# CAADIOESQV1_01-ADAPTADOR-MICRO-DIP28.net
KiCad netlist of a schematic drawn in Altium Designer
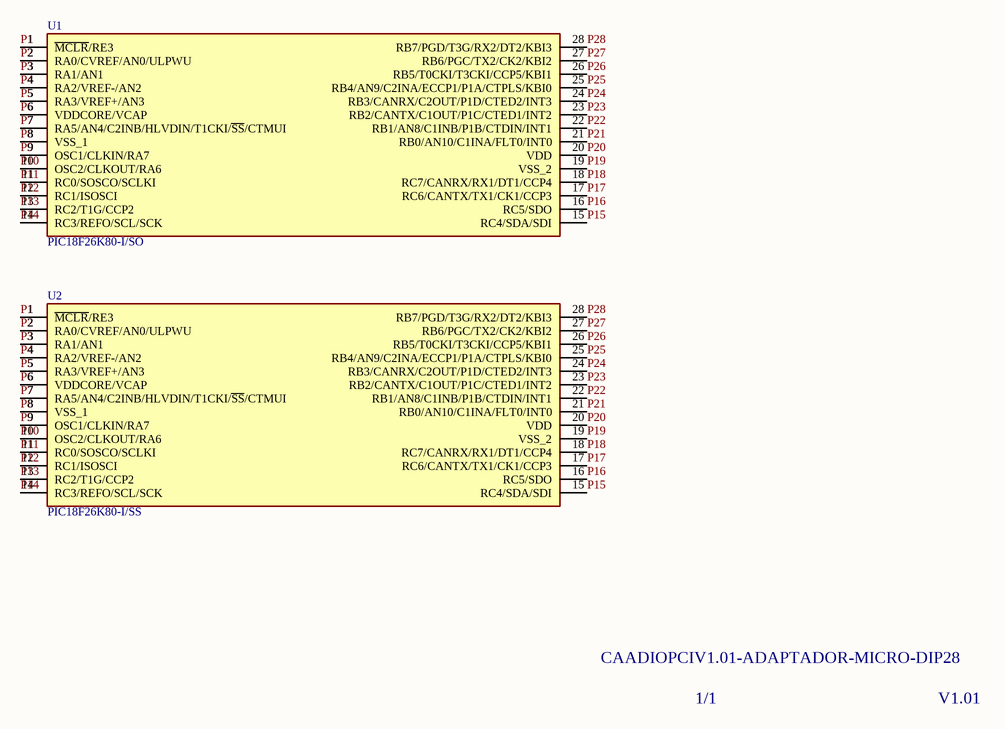
[diagram p0: CAADIOESQV1.01-ADAPTADOR-MICRO-DIP28.SchDoc]

(export (version "E")
  (design (tool "Eeschema 10.0.6"))
  (components
    (comp (ref "U1")
      (value "PIC18F26K80-I/SO")
      (footprint "SOIC-28")
      (description "Microcontrolador")
      (fields (field (name "MOUSER PART NUMBER") "579-PIC18F26K80-I/SO"))
      (libsource (lib "Lib SMD") (part "PIC18F26K80-I/SO"))
    )
    (comp (ref "U2")
      (value "PIC18F26K80-I/SS")
      (footprint "SSOP-28")
      (description "Microcontrolador")
      (fields (field (name "MOUSER PART NUMBER") "579-PIC18F26K80-I/SS"))
      (libsource (lib "Lib SMD") (part "PIC18F26K80-I/SS"))
    )
  )
  (nets
    (net (code "1") (name "/P1") (class "Default")
      (node (ref "U1") (pin "1") (pinfunction "~{MCLR}/RE3_1") (pintype "passive"))
      (node (ref "U2") (pin "1") (pinfunction "~{MCLR}/RE3_1") (pintype "passive"))
    )
    (net (code "2") (name "/P2") (class "Default")
      (node (ref "U1") (pin "2") (pinfunction "RA0/CVREF/AN0/ULPWU_2") (pintype "passive"))
      (node (ref "U2") (pin "2") (pinfunction "RA0/CVREF/AN0/ULPWU_2") (pintype "passive"))
    )
    (net (code "3") (name "/P3") (class "Default")
      (node (ref "U1") (pin "3") (pinfunction "RA1/AN1_3") (pintype "passive"))
      (node (ref "U2") (pin "3") (pinfunction "RA1/AN1_3") (pintype "passive"))
    )
    (net (code "4") (name "/P4") (class "Default")
      (node (ref "U1") (pin "4") (pinfunction "RA2/VREF-/AN2_4") (pintype "passive"))
      (node (ref "U2") (pin "4") (pinfunction "RA2/VREF-/AN2_4") (pintype "passive"))
    )
    (net (code "5") (name "/P5") (class "Default")
      (node (ref "U1") (pin "5") (pinfunction "RA3/VREF+/AN3_5") (pintype "passive"))
      (node (ref "U2") (pin "5") (pinfunction "RA3/VREF+/AN3_5") (pintype "passive"))
    )
    (net (code "6") (name "/P6") (class "Default")
      (node (ref "U1") (pin "6") (pinfunction "VDDCORE/VCAP_6") (pintype "passive"))
      (node (ref "U2") (pin "6") (pinfunction "VDDCORE/VCAP_6") (pintype "passive"))
    )
    (net (code "7") (name "/P7") (class "Default")
      (node (ref "U1") (pin "7") (pinfunction "RA5/AN4/C2INB/HLVDIN/T1CKI/~{SS}/CTMUI_7") (pintype "passive"))
      (node (ref "U2") (pin "7") (pinfunction "RA5/AN4/C2INB/HLVDIN/T1CKI/~{SS}/CTMUI_7") (pintype "passive"))
    )
    (net (code "8") (name "/P8") (class "Default")
      (node (ref "U1") (pin "8") (pinfunction "VSS_1_8") (pintype "passive"))
      (node (ref "U2") (pin "8") (pinfunction "VSS_1_8") (pintype "passive"))
    )
    (net (code "9") (name "/P9") (class "Default")
      (node (ref "U1") (pin "9") (pinfunction "OSC1/CLKIN/RA7_9") (pintype "passive"))
      (node (ref "U2") (pin "9") (pinfunction "OSC1/CLKIN/RA7_9") (pintype "passive"))
    )
    (net (code "10") (name "/P10") (class "Default")
      (node (ref "U1") (pin "10") (pinfunction "OSC2/CLKOUT/RA6_10") (pintype "passive"))
      (node (ref "U2") (pin "10") (pinfunction "OSC2/CLKOUT/RA6_10") (pintype "passive"))
    )
    (net (code "11") (name "/P11") (class "Default")
      (node (ref "U1") (pin "11") (pinfunction "RC0/SOSCO/SCLKI_11") (pintype "passive"))
      (node (ref "U2") (pin "11") (pinfunction "RC0/SOSCO/SCLKI_11") (pintype "passive"))
    )
    (net (code "12") (name "/P12") (class "Default")
      (node (ref "U1") (pin "12") (pinfunction "RC1/ISOSCI_12") (pintype "passive"))
      (node (ref "U2") (pin "12") (pinfunction "RC1/ISOSCI_12") (pintype "passive"))
    )
    (net (code "13") (name "/P13") (class "Default")
      (node (ref "U1") (pin "13") (pinfunction "RC2/T1G/CCP2_13") (pintype "passive"))
      (node (ref "U2") (pin "13") (pinfunction "RC2/T1G/CCP2_13") (pintype "passive"))
    )
    (net (code "14") (name "/P14") (class "Default")
      (node (ref "U1") (pin "14") (pinfunction "RC3/REFO/SCL/SCK_14") (pintype "passive"))
      (node (ref "U2") (pin "14") (pinfunction "RC3/REFO/SCL/SCK_14") (pintype "passive"))
    )
    (net (code "15") (name "/P15") (class "Default")
      (node (ref "U1") (pin "15") (pinfunction "RC4/SDA/SDI_15") (pintype "passive"))
      (node (ref "U2") (pin "15") (pinfunction "RC4/SDA/SDI_15") (pintype "passive"))
    )
    (net (code "16") (name "/P16") (class "Default")
      (node (ref "U1") (pin "16") (pinfunction "RC5/SDO_16") (pintype "passive"))
      (node (ref "U2") (pin "16") (pinfunction "RC5/SDO_16") (pintype "passive"))
    )
    (net (code "17") (name "/P17") (class "Default")
      (node (ref "U1") (pin "17") (pinfunction "RC6/CANTX/TX1/CK1/CCP3_17") (pintype "passive"))
      (node (ref "U2") (pin "17") (pinfunction "RC6/CANTX/TX1/CK1/CCP3_17") (pintype "passive"))
    )
    (net (code "18") (name "/P18") (class "Default")
      (node (ref "U1") (pin "18") (pinfunction "RC7/CANRX/RX1/DT1/CCP4_18") (pintype "passive"))
      (node (ref "U2") (pin "18") (pinfunction "RC7/CANRX/RX1/DT1/CCP4_18") (pintype "passive"))
    )
    (net (code "19") (name "/P19") (class "Default")
      (node (ref "U1") (pin "19") (pinfunction "VSS_2_19") (pintype "passive"))
      (node (ref "U2") (pin "19") (pinfunction "VSS_2_19") (pintype "passive"))
    )
    (net (code "20") (name "/P20") (class "Default")
      (node (ref "U1") (pin "20") (pinfunction "VDD_20") (pintype "passive"))
      (node (ref "U2") (pin "20") (pinfunction "VDD_20") (pintype "passive"))
    )
    (net (code "21") (name "/P21") (class "Default")
      (node (ref "U1") (pin "21") (pinfunction "RB0/AN10/C1INA/FLT0/INT0_21") (pintype "passive"))
      (node (ref "U2") (pin "21") (pinfunction "RB0/AN10/C1INA/FLT0/INT0_21") (pintype "passive"))
    )
    (net (code "22") (name "/P22") (class "Default")
      (node (ref "U1") (pin "22") (pinfunction "RB1/AN8/C1INB/P1B/CTDIN/INT1_22") (pintype "passive"))
      (node (ref "U2") (pin "22") (pinfunction "RB1/AN8/C1INB/P1B/CTDIN/INT1_22") (pintype "passive"))
    )
    (net (code "23") (name "/P23") (class "Default")
      (node (ref "U1") (pin "23") (pinfunction "RB2/CANTX/C1OUT/P1C/CTED1/INT2_23") (pintype "passive"))
      (node (ref "U2") (pin "23") (pinfunction "RB2/CANTX/C1OUT/P1C/CTED1/INT2_23") (pintype "passive"))
    )
    (net (code "24") (name "/P24") (class "Default")
      (node (ref "U1") (pin "24") (pinfunction "RB3/CANRX/C2OUT/P1D/CTED2/INT3_24") (pintype "passive"))
      (node (ref "U2") (pin "24") (pinfunction "RB3/CANRX/C2OUT/P1D/CTED2/INT3_24") (pintype "passive"))
    )
    (net (code "25") (name "/P25") (class "Default")
      (node (ref "U1") (pin "25") (pinfunction "RB4/AN9/C2INA/ECCP1/P1A/CTPLS/KBI0_25") (pintype "passive"))
      (node (ref "U2") (pin "25") (pinfunction "RB4/AN9/C2INA/ECCP1/P1A/CTPLS/KBI0_25") (pintype "passive"))
    )
    (net (code "26") (name "/P26") (class "Default")
      (node (ref "U1") (pin "26") (pinfunction "RB5/T0CKI/T3CKI/CCP5/KBI1_26") (pintype "passive"))
      (node (ref "U2") (pin "26") (pinfunction "RB5/T0CKI/T3CKI/CCP5/KBI1_26") (pintype "passive"))
    )
    (net (code "27") (name "/P27") (class "Default")
      (node (ref "U1") (pin "27") (pinfunction "RB6/PGC/TX2/CK2/KBI2_27") (pintype "passive"))
      (node (ref "U2") (pin "27") (pinfunction "RB6/PGC/TX2/CK2/KBI2_27") (pintype "passive"))
    )
    (net (code "28") (name "/P28") (class "Default")
      (node (ref "U1") (pin "28") (pinfunction "RB7/PGD/T3G/RX2/DT2/KBI3_28") (pintype "passive"))
      (node (ref "U2") (pin "28") (pinfunction "RB7/PGD/T3G/RX2/DT2/KBI3_28") (pintype "passive"))
    )
  )
)
